# Stick_of_Joy_with_headers.net
KiCad netlist of a schematic drawn in EAGLE
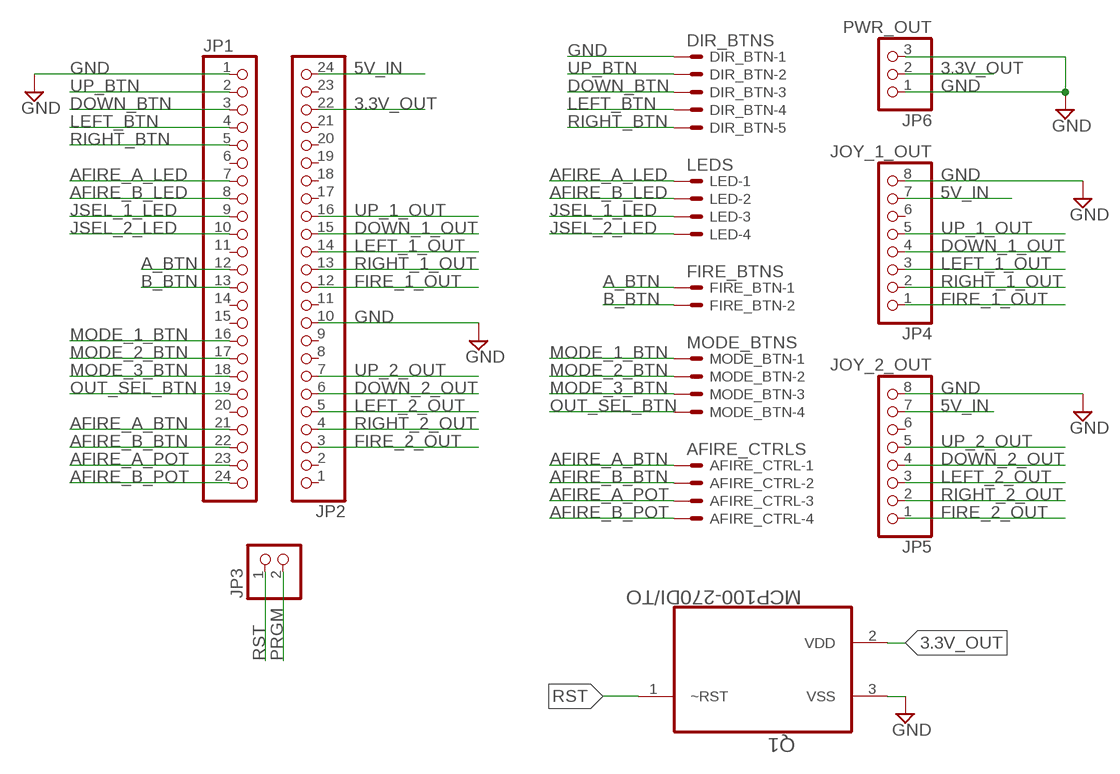
[diagram p0: schematic, sheet 1]

(export (version "E")
  (design (tool "Eeschema 10.0.6"))
  (components
    (comp (ref "AFIRE_CTRL")
      (value "AFIRE_CTRLS")
      (footprint "eagle-import:JST-XH-04-PACKAGE-ROUND-PAD")
      (libsource (lib "eagle-import") (part "JST-XH-04-PIN-ROUND-PAD"))
    )
    (comp (ref "DIR_BTN")
      (value "DIR_BTNS")
      (footprint "eagle-import:JST-XH-05-PACKAGE-ROUND-PAD")
      (libsource (lib "eagle-import") (part "JST-XH-05-PIN-ROUND-PAD"))
    )
    (comp (ref "FIRE_BTN")
      (value "FIRE_BTNS")
      (footprint "eagle-import:JST-XH-02-PACKAGE-ROUND-PAD")
      (libsource (lib "eagle-import") (part "JST-XH-02-PIN-ROUND-PAD"))
    )
    (comp (ref "JP1")
      (value "PINHD-1X24")
      (footprint "eagle-import:1X24")
      (libsource (lib "eagle-import") (part "PINHD-1X24"))
    )
    (comp (ref "JP2")
      (value "PINHD-1X24")
      (footprint "eagle-import:1X24")
      (libsource (lib "eagle-import") (part "PINHD-1X24"))
    )
    (comp (ref "JP3")
      (value "PINHD-1X2")
      (footprint "eagle-import:1X02")
      (libsource (lib "eagle-import") (part "PINHD-1X2"))
    )
    (comp (ref "JP4")
      (value "JOY_1_OUT")
      (footprint "eagle-import:1X08")
      (libsource (lib "eagle-import") (part "PINHD-1X8"))
    )
    (comp (ref "JP5")
      (value "JOY_2_OUT")
      (footprint "eagle-import:1X08")
      (libsource (lib "eagle-import") (part "PINHD-1X8"))
    )
    (comp (ref "JP6")
      (value "PWR_OUT")
      (footprint "eagle-import:1X03")
      (libsource (lib "eagle-import") (part "PINHD-1X3"))
    )
    (comp (ref "LED")
      (value "LEDS")
      (footprint "eagle-import:JST-XH-04-PACKAGE-ROUND-PAD")
      (libsource (lib "eagle-import") (part "JST-XH-04-PIN-ROUND-PAD"))
    )
    (comp (ref "MODE_BTN")
      (value "MODE_BTNS")
      (footprint "eagle-import:JST-XH-04-PACKAGE-ROUND-PAD")
      (libsource (lib "eagle-import") (part "JST-XH-04-PIN-ROUND-PAD"))
    )
    (comp (ref "Q1")
      (value "MCP100-270DI/TO")
      (footprint "eagle-import:TO127P254X495-3")
      (fields (field (name "DIGI-KEY_PART_NUMBER") "MCP100-270DI/TO-ND") (field (name "MF") "Microchip"))
      (libsource (lib "eagle-import") (part "MCP100-270DI/TO"))
    )
  )
  (nets
    (net (code "1") (name "/5V_IN") (class "Default")
      (node (ref "JP2") (pin "24") (pinfunction "24_24") (pintype "passive"))
      (node (ref "JP4") (pin "7") (pinfunction "7_7") (pintype "passive"))
      (node (ref "JP5") (pin "7") (pinfunction "7_7") (pintype "passive"))
    )
    (net (code "2") (name "/AFIRE_A_BTN") (class "Default")
      (node (ref "AFIRE_CTRL") (pin "1") (pinfunction "S_1") (pintype "passive"))
      (node (ref "JP1") (pin "21") (pinfunction "21_21") (pintype "passive"))
    )
    (net (code "3") (name "/AFIRE_A_LED") (class "Default")
      (node (ref "JP1") (pin "7") (pinfunction "7_7") (pintype "passive"))
      (node (ref "LED") (pin "1") (pinfunction "S_1") (pintype "passive"))
    )
    (net (code "4") (name "/AFIRE_A_POT") (class "Default")
      (node (ref "AFIRE_CTRL") (pin "3") (pinfunction "S_3") (pintype "passive"))
      (node (ref "JP1") (pin "23") (pinfunction "23_23") (pintype "passive"))
    )
    (net (code "5") (name "/AFIRE_B_BTN") (class "Default")
      (node (ref "AFIRE_CTRL") (pin "2") (pinfunction "S_2") (pintype "passive"))
      (node (ref "JP1") (pin "22") (pinfunction "22_22") (pintype "passive"))
    )
    (net (code "6") (name "/AFIRE_B_LED") (class "Default")
      (node (ref "JP1") (pin "8") (pinfunction "8_8") (pintype "passive"))
      (node (ref "LED") (pin "2") (pinfunction "S_2") (pintype "passive"))
    )
    (net (code "7") (name "/AFIRE_B_POT") (class "Default")
      (node (ref "AFIRE_CTRL") (pin "4") (pinfunction "S_4") (pintype "passive"))
      (node (ref "JP1") (pin "24") (pinfunction "24_24") (pintype "passive"))
    )
    (net (code "8") (name "/A_BTN") (class "Default")
      (node (ref "FIRE_BTN") (pin "1") (pinfunction "S_1") (pintype "passive"))
      (node (ref "JP1") (pin "12") (pinfunction "12_12") (pintype "passive"))
    )
    (net (code "9") (name "/B_BTN") (class "Default")
      (node (ref "FIRE_BTN") (pin "2") (pinfunction "S_2") (pintype "passive"))
      (node (ref "JP1") (pin "13") (pinfunction "13_13") (pintype "passive"))
    )
    (net (code "10") (name "/DOWN_1_OUT") (class "Default")
      (node (ref "JP2") (pin "15") (pinfunction "15_15") (pintype "passive"))
      (node (ref "JP4") (pin "4") (pinfunction "4_4") (pintype "passive"))
    )
    (net (code "11") (name "/DOWN_2_OUT") (class "Default")
      (node (ref "JP2") (pin "6") (pinfunction "6_6") (pintype "passive"))
      (node (ref "JP5") (pin "4") (pinfunction "4_4") (pintype "passive"))
    )
    (net (code "12") (name "/DOWN_BTN") (class "Default")
      (node (ref "DIR_BTN") (pin "3") (pinfunction "S_3") (pintype "passive"))
      (node (ref "JP1") (pin "3") (pinfunction "3_3") (pintype "passive"))
    )
    (net (code "13") (name "/FIRE_1_OUT") (class "Default")
      (node (ref "JP2") (pin "12") (pinfunction "12_12") (pintype "passive"))
      (node (ref "JP4") (pin "1") (pinfunction "1_1") (pintype "passive"))
    )
    (net (code "14") (name "/FIRE_2_OUT") (class "Default")
      (node (ref "JP2") (pin "3") (pinfunction "3_3") (pintype "passive"))
      (node (ref "JP5") (pin "1") (pinfunction "1_1") (pintype "passive"))
    )
    (net (code "15") (name "/JSEL_1_LED") (class "Default")
      (node (ref "JP1") (pin "9") (pinfunction "9_9") (pintype "passive"))
      (node (ref "LED") (pin "3") (pinfunction "S_3") (pintype "passive"))
    )
    (net (code "16") (name "/JSEL_2_LED") (class "Default")
      (node (ref "JP1") (pin "10") (pinfunction "10_10") (pintype "passive"))
      (node (ref "LED") (pin "4") (pinfunction "S_4") (pintype "passive"))
    )
    (net (code "17") (name "/LEFT_1_OUT") (class "Default")
      (node (ref "JP2") (pin "14") (pinfunction "14_14") (pintype "passive"))
      (node (ref "JP4") (pin "3") (pinfunction "3_3") (pintype "passive"))
    )
    (net (code "18") (name "/LEFT_2_OUT") (class "Default")
      (node (ref "JP2") (pin "5") (pinfunction "5_5") (pintype "passive"))
      (node (ref "JP5") (pin "3") (pinfunction "3_3") (pintype "passive"))
    )
    (net (code "19") (name "/LEFT_BTN") (class "Default")
      (node (ref "DIR_BTN") (pin "4") (pinfunction "S_4") (pintype "passive"))
      (node (ref "JP1") (pin "4") (pinfunction "4_4") (pintype "passive"))
    )
    (net (code "20") (name "/MODE_1_BTN") (class "Default")
      (node (ref "JP1") (pin "16") (pinfunction "16_16") (pintype "passive"))
      (node (ref "MODE_BTN") (pin "1") (pinfunction "S_1") (pintype "passive"))
    )
    (net (code "21") (name "/MODE_2_BTN") (class "Default")
      (node (ref "JP1") (pin "17") (pinfunction "17_17") (pintype "passive"))
      (node (ref "MODE_BTN") (pin "2") (pinfunction "S_2") (pintype "passive"))
    )
    (net (code "22") (name "/MODE_3_BTN") (class "Default")
      (node (ref "JP1") (pin "18") (pinfunction "18_18") (pintype "passive"))
      (node (ref "MODE_BTN") (pin "3") (pinfunction "S_3") (pintype "passive"))
    )
    (net (code "23") (name "/OUT_SEL_BTN") (class "Default")
      (node (ref "JP1") (pin "19") (pinfunction "19_19") (pintype "passive"))
      (node (ref "MODE_BTN") (pin "4") (pinfunction "S_4") (pintype "passive"))
    )
    (net (code "24") (name "/PRGM") (class "Default")
      (node (ref "JP3") (pin "2") (pinfunction "2_2") (pintype "passive"))
    )
    (net (code "25") (name "/RIGHT_1_OUT") (class "Default")
      (node (ref "JP2") (pin "13") (pinfunction "13_13") (pintype "passive"))
      (node (ref "JP4") (pin "2") (pinfunction "2_2") (pintype "passive"))
    )
    (net (code "26") (name "/RIGHT_2_OUT") (class "Default")
      (node (ref "JP2") (pin "4") (pinfunction "4_4") (pintype "passive"))
      (node (ref "JP5") (pin "2") (pinfunction "2_2") (pintype "passive"))
    )
    (net (code "27") (name "/RIGHT_BTN") (class "Default")
      (node (ref "DIR_BTN") (pin "5") (pinfunction "S_5") (pintype "passive"))
      (node (ref "JP1") (pin "5") (pinfunction "5_5") (pintype "passive"))
    )
    (net (code "28") (name "/UP_1_OUT") (class "Default")
      (node (ref "JP2") (pin "16") (pinfunction "16_16") (pintype "passive"))
      (node (ref "JP4") (pin "5") (pinfunction "5_5") (pintype "passive"))
    )
    (net (code "29") (name "/UP_2_OUT") (class "Default")
      (node (ref "JP2") (pin "7") (pinfunction "7_7") (pintype "passive"))
      (node (ref "JP5") (pin "5") (pinfunction "5_5") (pintype "passive"))
    )
    (net (code "30") (name "/UP_BTN") (class "Default")
      (node (ref "DIR_BTN") (pin "2") (pinfunction "S_2") (pintype "passive"))
      (node (ref "JP1") (pin "2") (pinfunction "2_2") (pintype "passive"))
    )
    (net (code "31") (name "3.3V_OUT") (class "Default")
      (node (ref "JP2") (pin "22") (pinfunction "22_22") (pintype "passive"))
      (node (ref "JP6") (pin "2") (pinfunction "2_2") (pintype "passive"))
      (node (ref "Q1") (pin "2") (pinfunction "VDD_2") (pintype "power_in"))
    )
    (net (code "32") (name "GND") (class "Default")
      (node (ref "DIR_BTN") (pin "1") (pinfunction "S_1") (pintype "passive"))
      (node (ref "JP1") (pin "1") (pinfunction "1_1") (pintype "passive"))
      (node (ref "JP2") (pin "10") (pinfunction "10_10") (pintype "passive"))
      (node (ref "JP4") (pin "8") (pinfunction "8_8") (pintype "passive"))
      (node (ref "JP5") (pin "8") (pinfunction "8_8") (pintype "passive"))
      (node (ref "JP6") (pin "1") (pinfunction "1_1") (pintype "passive"))
      (node (ref "JP6") (pin "3") (pinfunction "3_3") (pintype "passive"))
      (node (ref "Q1") (pin "3") (pinfunction "VSS_3") (pintype "passive"))
    )
    (net (code "33") (name "RST") (class "Default")
      (node (ref "JP3") (pin "1") (pinfunction "1_1") (pintype "passive"))
      (node (ref "Q1") (pin "1") (pinfunction "~{RST}_1") (pintype "output"))
    )
    (net (code "34") (name "unconnected-(JP1-Pad6)") (class "Default")
      (node (ref "JP1") (pin "6") (pinfunction "6_6") (pintype "passive"))
    )
    (net (code "35") (name "unconnected-(JP1-Pad11)") (class "Default")
      (node (ref "JP1") (pin "11") (pinfunction "11_11") (pintype "passive"))
    )
    (net (code "36") (name "unconnected-(JP1-Pad14)") (class "Default")
      (node (ref "JP1") (pin "14") (pinfunction "14_14") (pintype "passive"))
    )
    (net (code "37") (name "unconnected-(JP1-Pad15)") (class "Default")
      (node (ref "JP1") (pin "15") (pinfunction "15_15") (pintype "passive"))
    )
    (net (code "38") (name "unconnected-(JP1-Pad20)") (class "Default")
      (node (ref "JP1") (pin "20") (pinfunction "20_20") (pintype "passive"))
    )
    (net (code "39") (name "unconnected-(JP2-Pad1)") (class "Default")
      (node (ref "JP2") (pin "1") (pinfunction "1_1") (pintype "passive"))
    )
    (net (code "40") (name "unconnected-(JP2-Pad2)") (class "Default")
      (node (ref "JP2") (pin "2") (pinfunction "2_2") (pintype "passive"))
    )
    (net (code "41") (name "unconnected-(JP2-Pad8)") (class "Default")
      (node (ref "JP2") (pin "8") (pinfunction "8_8") (pintype "passive"))
    )
    (net (code "42") (name "unconnected-(JP2-Pad9)") (class "Default")
      (node (ref "JP2") (pin "9") (pinfunction "9_9") (pintype "passive"))
    )
    (net (code "43") (name "unconnected-(JP2-Pad11)") (class "Default")
      (node (ref "JP2") (pin "11") (pinfunction "11_11") (pintype "passive"))
    )
    (net (code "44") (name "unconnected-(JP2-Pad17)") (class "Default")
      (node (ref "JP2") (pin "17") (pinfunction "17_17") (pintype "passive"))
    )
    (net (code "45") (name "unconnected-(JP2-Pad18)") (class "Default")
      (node (ref "JP2") (pin "18") (pinfunction "18_18") (pintype "passive"))
    )
    (net (code "46") (name "unconnected-(JP2-Pad19)") (class "Default")
      (node (ref "JP2") (pin "19") (pinfunction "19_19") (pintype "passive"))
    )
    (net (code "47") (name "unconnected-(JP2-Pad20)") (class "Default")
      (node (ref "JP2") (pin "20") (pinfunction "20_20") (pintype "passive"))
    )
    (net (code "48") (name "unconnected-(JP2-Pad21)") (class "Default")
      (node (ref "JP2") (pin "21") (pinfunction "21_21") (pintype "passive"))
    )
    (net (code "49") (name "unconnected-(JP2-Pad23)") (class "Default")
      (node (ref "JP2") (pin "23") (pinfunction "23_23") (pintype "passive"))
    )
    (net (code "50") (name "unconnected-(JP4-Pad6)") (class "Default")
      (node (ref "JP4") (pin "6") (pinfunction "6_6") (pintype "passive"))
    )
    (net (code "51") (name "unconnected-(JP5-Pad6)") (class "Default")
      (node (ref "JP5") (pin "6") (pinfunction "6_6") (pintype "passive"))
    )
  )
)
